# EVB_Gatedriver.net
KiCad netlist of a schematic drawn in Altium Designer
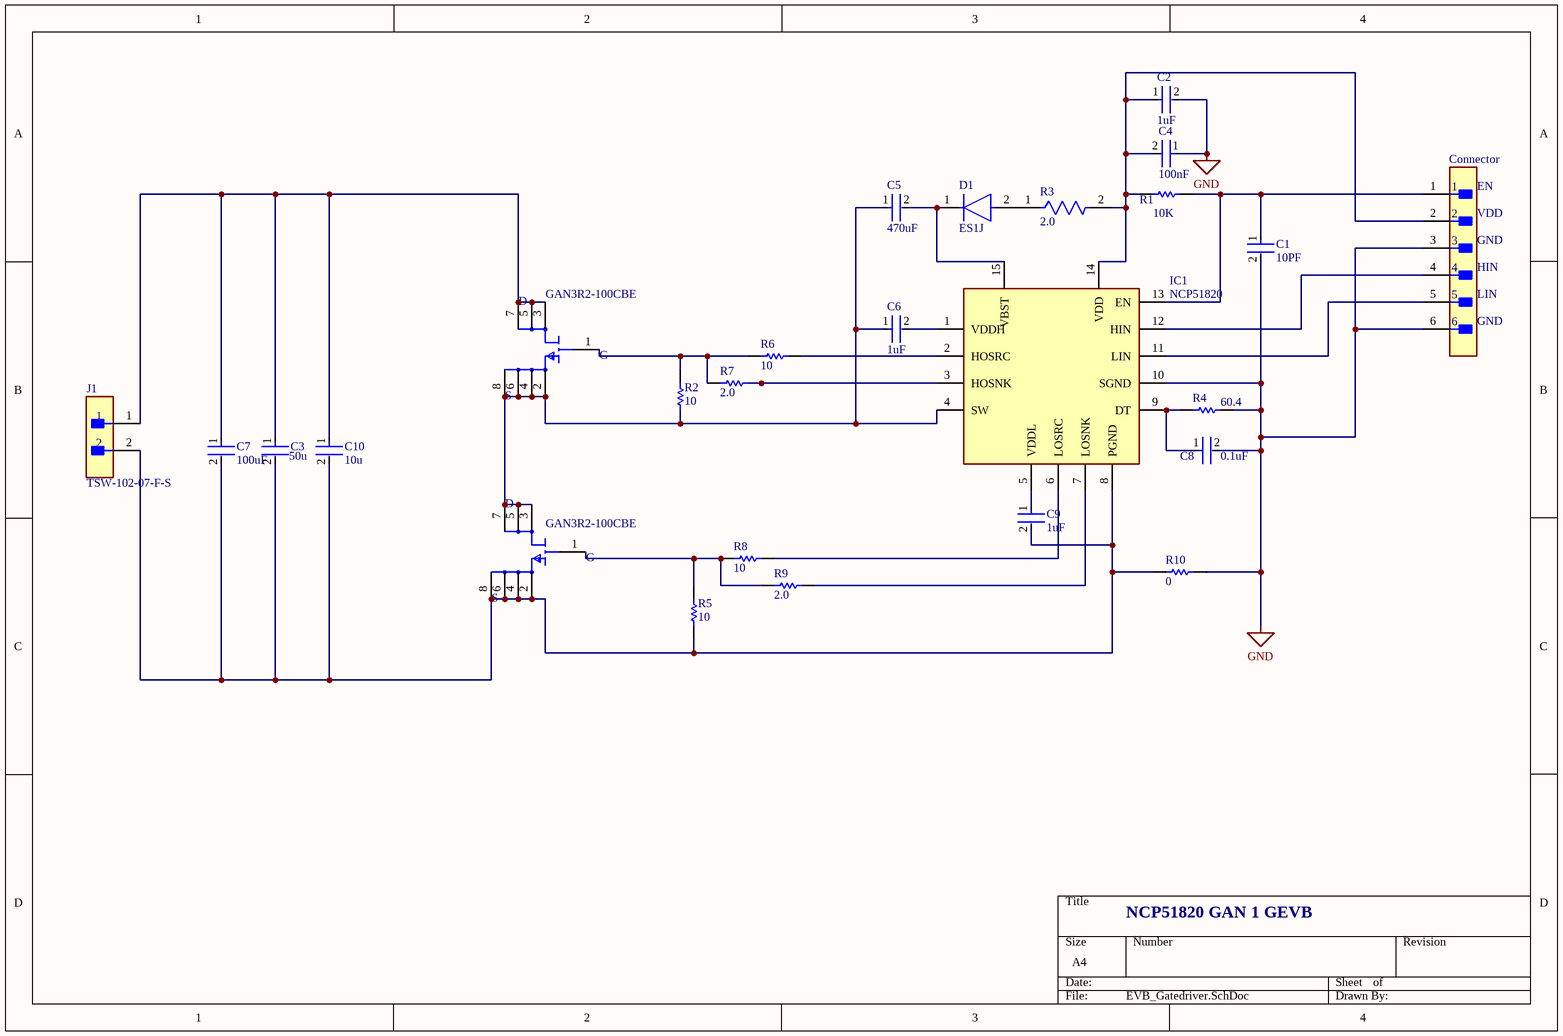
[diagram p0: EVB_Gatedriver.SchDoc]

(export (version "E")
  (design (tool "Eeschema 10.0.6"))
  (components
    (comp (ref "1")
      (value "GAN3R2-100CBE")
      (footprint "FP-WLCSP8-SOT8072-MFG")
      (libsource (lib "Alpha_library") (part "GAN3R2-100CBE_1"))
    )
    (comp (ref "2")
      (value "GAN3R2-100CBE")
      (footprint "FP-WLCSP8-SOT8072-MFG")
      (libsource (lib "Alpha_library") (part "GAN3R2-100CBE_1"))
    )
    (comp (ref "C1")
      (value "10PF")
      (footprint "FP-C1206C-EB-MFG")
      (description "CAP CER 10PF 50V C0G/NP0 1206")
      (fields
        (field (name "OCTOPART") "https://octopart.com/c1206c100j5gactu-kemet-87062")
        (field (name "MANUFACTURER PART NUMBER") "C1206C100J5GACTU")
      )
      (libsource (lib "Altium Content Vault") (part "b4654b650e69147ec39a6b967a45e02"))
    )
    (comp (ref "C2")
      (value "1uF")
      (footprint "FP-CC1206-1_25-MFG")
      (description "CAP CER 1UF 25V X7R 1206")
      (fields
        (field (name "MANUFACTURER PART NUMBER") "CC1206KKX7R8BB105")
        (field (name "OCTOPART") "https://octopart.com/cc1206kkx7r8bb105-yageo-11543785")
      )
      (libsource (lib "Altium Content Vault") (part "11868f565c42a9108669ba33697ecf6"))
    )
    (comp (ref "C3")
      (value "50u")
      (footprint "FP-CGA5L-0_3-0_1-IPC_B")
      (description "Cap Ceramic 100nF 450V X7T 10% Pad SMD 1206 +125°C Automotive T/R")
      (fields (field (name "TOLERANCE") "10%"))
      (libsource (lib "Altium Content Vault") (part "b4654b650e69147ec39a6b967a45e02"))
    )
    (comp (ref "C4")
      (value "100nF")
      (footprint "FP-1206-L_3_2_0_15-W_1_6-MFG")
      (description "None")
      (libsource (lib "Altium Content Vault") (part "02cd4be3c70576c341d710602a673aa"))
    )
    (comp (ref "C5")
      (value "470uF")
      (footprint "FP-C1206C-EB-MFG")
      (description "CAP CER 0.47UF 25V X5R 1206")
      (fields
        (field (name "MANUFACTURER") "KEMET")
        (field (name "OCTOPART") "https://octopart.com/c1206c474k3pactu-kemet-16430430")
      )
      (libsource (lib "Altium Content Vault") (part "b4654b650e69147ec39a6b967a45e02"))
    )
    (comp (ref "C6")
      (value "1uF")
      (footprint "FP-1206-L_3_2_0_15-W_1_6-IPC_A")
      (description "None")
      (fields (field (name "TOLERANCE") "10%") (field (name "VOLTAGE") "25V"))
      (libsource (lib "Altium Content Vault") (part "02cd4be3c70576c341d710602a673aa"))
    )
    (comp (ref "C7")
      (value "100uF")
      (footprint "FP-CGA5L-0_3-0_1-IPC_B")
      (description "Cap Ceramic 100nF 450V X7T 10% Pad SMD 1206 +125°C Automotive T/R")
      (fields (field (name "TOLERANCE") "10%"))
      (libsource (lib "Altium Content Vault") (part "b4654b650e69147ec39a6b967a45e02"))
    )
    (comp (ref "C8")
      (value "0.1uF")
      (footprint "FP-C1206C-EB-MFG")
      (description "CAP CER 0.1UF 25V 10% X7R 1206")
      (fields
        (field (name "MANUFACTURER") "KEMET")
        (field (name "OCTOPART") "https://octopart.com/c1206c104k3ractu-kemet-9144317")
      )
      (libsource (lib "Altium Content Vault") (part "b4654b650e69147ec39a6b967a45e02"))
    )
    (comp (ref "C9")
      (value "1uF")
      (footprint "FP-1206-L_3_2_0_15-W_1_6-IPC_A")
      (description "None")
      (fields (field (name "TOLERANCE") "10%") (field (name "VOLTAGE") "25V"))
      (libsource (lib "Altium Content Vault") (part "02cd4be3c70576c341d710602a673aa"))
    )
    (comp (ref "C10")
      (value "10u")
      (footprint "FP-CGA5L-0_3-0_1-IPC_B")
      (description "Cap Ceramic 100nF 450V X7T 10% Pad SMD 1206 +125°C Automotive T/R")
      (fields (field (name "TOLERANCE") "10%"))
      (libsource (lib "Altium Content Vault") (part "b4654b650e69147ec39a6b967a45e02"))
    )
    (comp (ref "Connector")
      (value "~")
      (footprint "FP-22-28-4060-MFG")
      (description "CONN HEADER VERT 6POS 2.54MM")
      (fields (field (name "MPN") "22-28-4060"))
      (libsource (lib "Altium Content Vault") (part "f2cb566baf1c37ab5a3b8e90bbeafd6"))
    )
    (comp (ref "D1")
      (value "ES1J")
      (footprint "FP-403AE-MFG")
      (description "DIODE GEN PURP 400V 1A SMA")
      (fields
        (field (name "OCTOPART") "https://octopart.com/es1g-on+semiconductor-84324858")
        (field (name "MANUFACTURER") "ON Semiconductor")
      )
      (libsource (lib "Altium Content Vault") (part "d7152d700b627762746794eb795d46e"))
    )
    (comp (ref "IC1")
      (value "NCP51820")
      (footprint "NCP51820")
      (description "Integrated Circuit")
      (libsource (lib "Alpha_library") (part "NCP51820"))
    )
    (comp (ref "J1")
      (value "TSW-102-07-F-S")
      (footprint "FP-TSW-102-07-F-S-MFG")
      (description "CONN HEADER VERT 2POS 2.54MM")
      (libsource (lib "Altium Content Vault") (part "3bc925449376181038e59eaffc5286c"))
    )
    (comp (ref "R1")
      (value "10K")
      (footprint "RESC3116X65X40ML10T20")
      (description "Chip Resistor, 10 KOhm, +/- 1%, 0.25 W, -55 to 155 degC, 1206 (3216 Metric), RoHS, Tape and Reel")
      (fields (field (name "TOLERANCE") "1%") (field (name "MANUFACTURER") "Yageo"))
      (libsource (lib "Altium Content Vault") (part "RES-2"))
    )
    (comp (ref "R2")
      (value "10")
      (footprint "RESC3116X65X40ML10T20")
      (description "Chip Resistor, 10 KOhm, +/- 1%, 0.25 W, -55 to 155 degC, 1206 (3216 Metric), RoHS, Tape and Reel")
      (fields (field (name "TOLERANCE") "1%") (field (name "MANUFACTURER") "Yageo"))
      (libsource (lib "Altium Content Vault") (part "RES-2"))
    )
    (comp (ref "R3")
      (value "2.0")
      (footprint "FP-RMCF1206-IPC_C")
      (description "RES 2 OHM 1% 1/4W 1206")
      (fields (field (name "TOLERANCE") "1%"))
      (libsource (lib "Altium Content Vault") (part "1029c3af85768c4190bb7ad29bc67b5"))
    )
    (comp (ref "R4")
      (value "60.4")
      (footprint "RESC3116X65X40LL10T20")
      (fields (field (name "PART NUMBER") "RC1206FR-1360R4L") (field (name "MANUFACTURER") "Yageo"))
      (libsource (lib "Altium Content Vault") (part "RES"))
    )
    (comp (ref "R5")
      (value "10")
      (footprint "RESC3116X65X40ML10T20")
      (description "Chip Resistor, 10 KOhm, +/- 1%, 0.25 W, -55 to 155 degC, 1206 (3216 Metric), RoHS, Tape and Reel")
      (fields (field (name "TOLERANCE") "1%") (field (name "MANUFACTURER") "Yageo"))
      (libsource (lib "Altium Content Vault") (part "RES-2"))
    )
    (comp (ref "R6")
      (value "10")
      (footprint "RESC3116X65X40NL10T20")
      (fields (field (name "PART NUMBER") "RC1206FR-1310RL") (field (name "MANUFACTURER") "Yageo"))
      (libsource (lib "Altium Content Vault") (part "RES"))
    )
    (comp (ref "R7")
      (value "2.0")
      (footprint "RESC3116X65X40NL10T20")
      (fields (field (name "MANUFACTURER") "Yageo") (field (name "PART NUMBER") "RC1206JR-072RL"))
      (libsource (lib "Altium Content Vault") (part "RES"))
    )
    (comp (ref "R8")
      (value "10")
      (footprint "RESC3116X65X40NL10T20")
      (fields (field (name "PART NUMBER") "RC1206FR-1310RL") (field (name "MANUFACTURER") "Yageo"))
      (libsource (lib "Altium Content Vault") (part "RES"))
    )
    (comp (ref "R9")
      (value "2.0")
      (footprint "RESC3116X65X40NL10T20")
      (fields (field (name "MANUFACTURER") "Yageo") (field (name "PART NUMBER") "RC1206JR-072RL"))
      (libsource (lib "Altium Content Vault") (part "RES"))
    )
    (comp (ref "R10")
      (value "0")
      (footprint "RESC1608X55X25ML10T15")
      (description "Chip Resistor, 0 Ohm, +/- 5%, 0.1 W, -55 to 155 degC, 0603 (1608 Metric), RoHS, Tape and Reel")
      (fields (field (name "TOLERANCE") "5%") (field (name "MANUFACTURER") "Yageo"))
      (libsource (lib "Altium Content Vault") (part "RES-2"))
    )
  )
  (nets
    (net (code "1") (name "GND") (class "Default")
      (node (ref "C1") (pin "2") (pinfunction "2_2") (pintype "passive"))
      (node (ref "C2") (pin "2") (pinfunction "2_2") (pintype "passive"))
      (node (ref "C4") (pin "1") (pinfunction "1_1") (pintype "passive"))
      (node (ref "C8") (pin "2") (pinfunction "2_2") (pintype "passive"))
      (node (ref "Connector") (pin "3") (pinfunction "3_3") (pintype "passive"))
      (node (ref "Connector") (pin "6") (pinfunction "6_6") (pintype "passive"))
      (node (ref "IC1") (pin "10") (pinfunction "SGND_10") (pintype "passive"))
      (node (ref "R10") (pin "2") (pinfunction "2_2") (pintype "passive"))
      (node (ref "R4") (pin "2") (pinfunction "2_2") (pintype "passive"))
    )
    (net (code "2") (name "Net-(1-D-Pad3)") (class "Default")
      (node (ref "1") (pin "3") (pinfunction "D_3") (pintype "passive"))
      (node (ref "1") (pin "5") (pinfunction "D_5") (pintype "passive"))
      (node (ref "1") (pin "7") (pinfunction "D_7") (pintype "passive"))
      (node (ref "C10") (pin "1") (pinfunction "1_1") (pintype "passive"))
      (node (ref "C3") (pin "1") (pinfunction "1_1") (pintype "passive"))
      (node (ref "C7") (pin "1") (pinfunction "1_1") (pintype "passive"))
      (node (ref "J1") (pin "1") (pinfunction "1_1") (pintype "passive"))
    )
    (net (code "3") (name "Net-(1-G)") (class "Default")
      (node (ref "1") (pin "1") (pinfunction "G_1") (pintype "passive"))
      (node (ref "R2") (pin "2") (pinfunction "2_2") (pintype "passive"))
      (node (ref "R6") (pin "1") (pinfunction "1_1") (pintype "passive"))
      (node (ref "R7") (pin "1") (pinfunction "1_1") (pintype "passive"))
    )
    (net (code "4") (name "Net-(2-G)") (class "Default")
      (node (ref "2") (pin "1") (pinfunction "G_1") (pintype "passive"))
      (node (ref "R5") (pin "2") (pinfunction "2_2") (pintype "passive"))
      (node (ref "R8") (pin "1") (pinfunction "1_1") (pintype "passive"))
      (node (ref "R9") (pin "1") (pinfunction "1_1") (pintype "passive"))
    )
    (net (code "5") (name "Net-(D1-A)") (class "Default")
      (node (ref "D1") (pin "2") (pinfunction "A_2") (pintype "passive"))
      (node (ref "R3") (pin "1") (pinfunction "1_1") (pintype "passive"))
    )
    (net (code "6") (name "Net-(D1-C)") (class "Default")
      (node (ref "C5") (pin "2") (pinfunction "2_2") (pintype "passive"))
      (node (ref "D1") (pin "1") (pinfunction "C_1") (pintype "passive"))
      (node (ref "IC1") (pin "15") (pinfunction "VBST_15") (pintype "passive"))
    )
    (net (code "7") (name "Net-(IC1-DT)") (class "Default")
      (node (ref "C8") (pin "1") (pinfunction "1_1") (pintype "passive"))
      (node (ref "IC1") (pin "9") (pinfunction "DT_9") (pintype "passive"))
      (node (ref "R4") (pin "1") (pinfunction "1_1") (pintype "passive"))
    )
    (net (code "8") (name "Net-(IC1-EN)") (class "Default")
      (node (ref "C1") (pin "1") (pinfunction "1_1") (pintype "passive"))
      (node (ref "Connector") (pin "1") (pinfunction "1_1") (pintype "passive"))
      (node (ref "IC1") (pin "13") (pinfunction "EN_13") (pintype "passive"))
      (node (ref "R1") (pin "2") (pinfunction "2_2") (pintype "passive"))
    )
    (net (code "9") (name "Net-(IC1-HIN)") (class "Default")
      (node (ref "Connector") (pin "4") (pinfunction "4_4") (pintype "passive"))
      (node (ref "IC1") (pin "12") (pinfunction "HIN_12") (pintype "passive"))
    )
    (net (code "10") (name "Net-(IC1-HOSNK)") (class "Default")
      (node (ref "IC1") (pin "3") (pinfunction "HOSNK_3") (pintype "passive"))
      (node (ref "R7") (pin "2") (pinfunction "2_2") (pintype "passive"))
    )
    (net (code "11") (name "Net-(IC1-HOSRC)") (class "Default")
      (node (ref "IC1") (pin "2") (pinfunction "HOSRC_2") (pintype "passive"))
      (node (ref "R6") (pin "2") (pinfunction "2_2") (pintype "passive"))
    )
    (net (code "12") (name "Net-(IC1-LIN)") (class "Default")
      (node (ref "Connector") (pin "5") (pinfunction "5_5") (pintype "passive"))
      (node (ref "IC1") (pin "11") (pinfunction "LIN_11") (pintype "passive"))
    )
    (net (code "13") (name "Net-(IC1-LOSNK)") (class "Default")
      (node (ref "IC1") (pin "7") (pinfunction "LOSNK_7") (pintype "passive"))
      (node (ref "R9") (pin "2") (pinfunction "2_2") (pintype "passive"))
    )
    (net (code "14") (name "Net-(IC1-LOSRC)") (class "Default")
      (node (ref "IC1") (pin "6") (pinfunction "LOSRC_6") (pintype "passive"))
      (node (ref "R8") (pin "2") (pinfunction "2_2") (pintype "passive"))
    )
    (net (code "15") (name "Net-(IC1-PGND)") (class "Default")
      (node (ref "2") (pin "2") (pinfunction "S_2") (pintype "passive"))
      (node (ref "2") (pin "4") (pinfunction "S_4") (pintype "passive"))
      (node (ref "2") (pin "6") (pinfunction "S_6") (pintype "passive"))
      (node (ref "2") (pin "8") (pinfunction "S_8") (pintype "passive"))
      (node (ref "C10") (pin "2") (pinfunction "2_2") (pintype "passive"))
      (node (ref "C3") (pin "2") (pinfunction "2_2") (pintype "passive"))
      (node (ref "C7") (pin "2") (pinfunction "2_2") (pintype "passive"))
      (node (ref "C9") (pin "2") (pinfunction "2_2") (pintype "passive"))
      (node (ref "IC1") (pin "8") (pinfunction "PGND_8") (pintype "passive"))
      (node (ref "J1") (pin "2") (pinfunction "2_2") (pintype "passive"))
      (node (ref "R10") (pin "1") (pinfunction "1_1") (pintype "passive"))
      (node (ref "R5") (pin "1") (pinfunction "1_1") (pintype "passive"))
    )
    (net (code "16") (name "Net-(IC1-SW)") (class "Default")
      (node (ref "1") (pin "2") (pinfunction "S_2") (pintype "passive"))
      (node (ref "1") (pin "4") (pinfunction "S_4") (pintype "passive"))
      (node (ref "1") (pin "6") (pinfunction "S_6") (pintype "passive"))
      (node (ref "1") (pin "8") (pinfunction "S_8") (pintype "passive"))
      (node (ref "2") (pin "3") (pinfunction "D_3") (pintype "passive"))
      (node (ref "2") (pin "5") (pinfunction "D_5") (pintype "passive"))
      (node (ref "2") (pin "7") (pinfunction "D_7") (pintype "passive"))
      (node (ref "C5") (pin "1") (pinfunction "1_1") (pintype "passive"))
      (node (ref "C6") (pin "1") (pinfunction "1_1") (pintype "passive"))
      (node (ref "IC1") (pin "4") (pinfunction "SW_4") (pintype "passive"))
      (node (ref "R2") (pin "1") (pinfunction "1_1") (pintype "passive"))
    )
    (net (code "17") (name "Net-(IC1-VDD)") (class "Default")
      (node (ref "C2") (pin "1") (pinfunction "1_1") (pintype "passive"))
      (node (ref "C4") (pin "2") (pinfunction "2_2") (pintype "passive"))
      (node (ref "Connector") (pin "2") (pinfunction "2_2") (pintype "passive"))
      (node (ref "IC1") (pin "14") (pinfunction "VDD_14") (pintype "passive"))
      (node (ref "R1") (pin "1") (pinfunction "1_1") (pintype "passive"))
      (node (ref "R3") (pin "2") (pinfunction "2_2") (pintype "passive"))
    )
    (net (code "18") (name "Net-(IC1-VDDH)") (class "Default")
      (node (ref "C6") (pin "2") (pinfunction "2_2") (pintype "passive"))
      (node (ref "IC1") (pin "1") (pinfunction "VDDH_1") (pintype "passive"))
    )
    (net (code "19") (name "Net-(IC1-VDDL)") (class "Default")
      (node (ref "C9") (pin "1") (pinfunction "1_1") (pintype "passive"))
      (node (ref "IC1") (pin "5") (pinfunction "VDDL_5") (pintype "passive"))
    )
  )
)
